# IOPower.net
KiCad netlist of a schematic drawn in Altium Designer
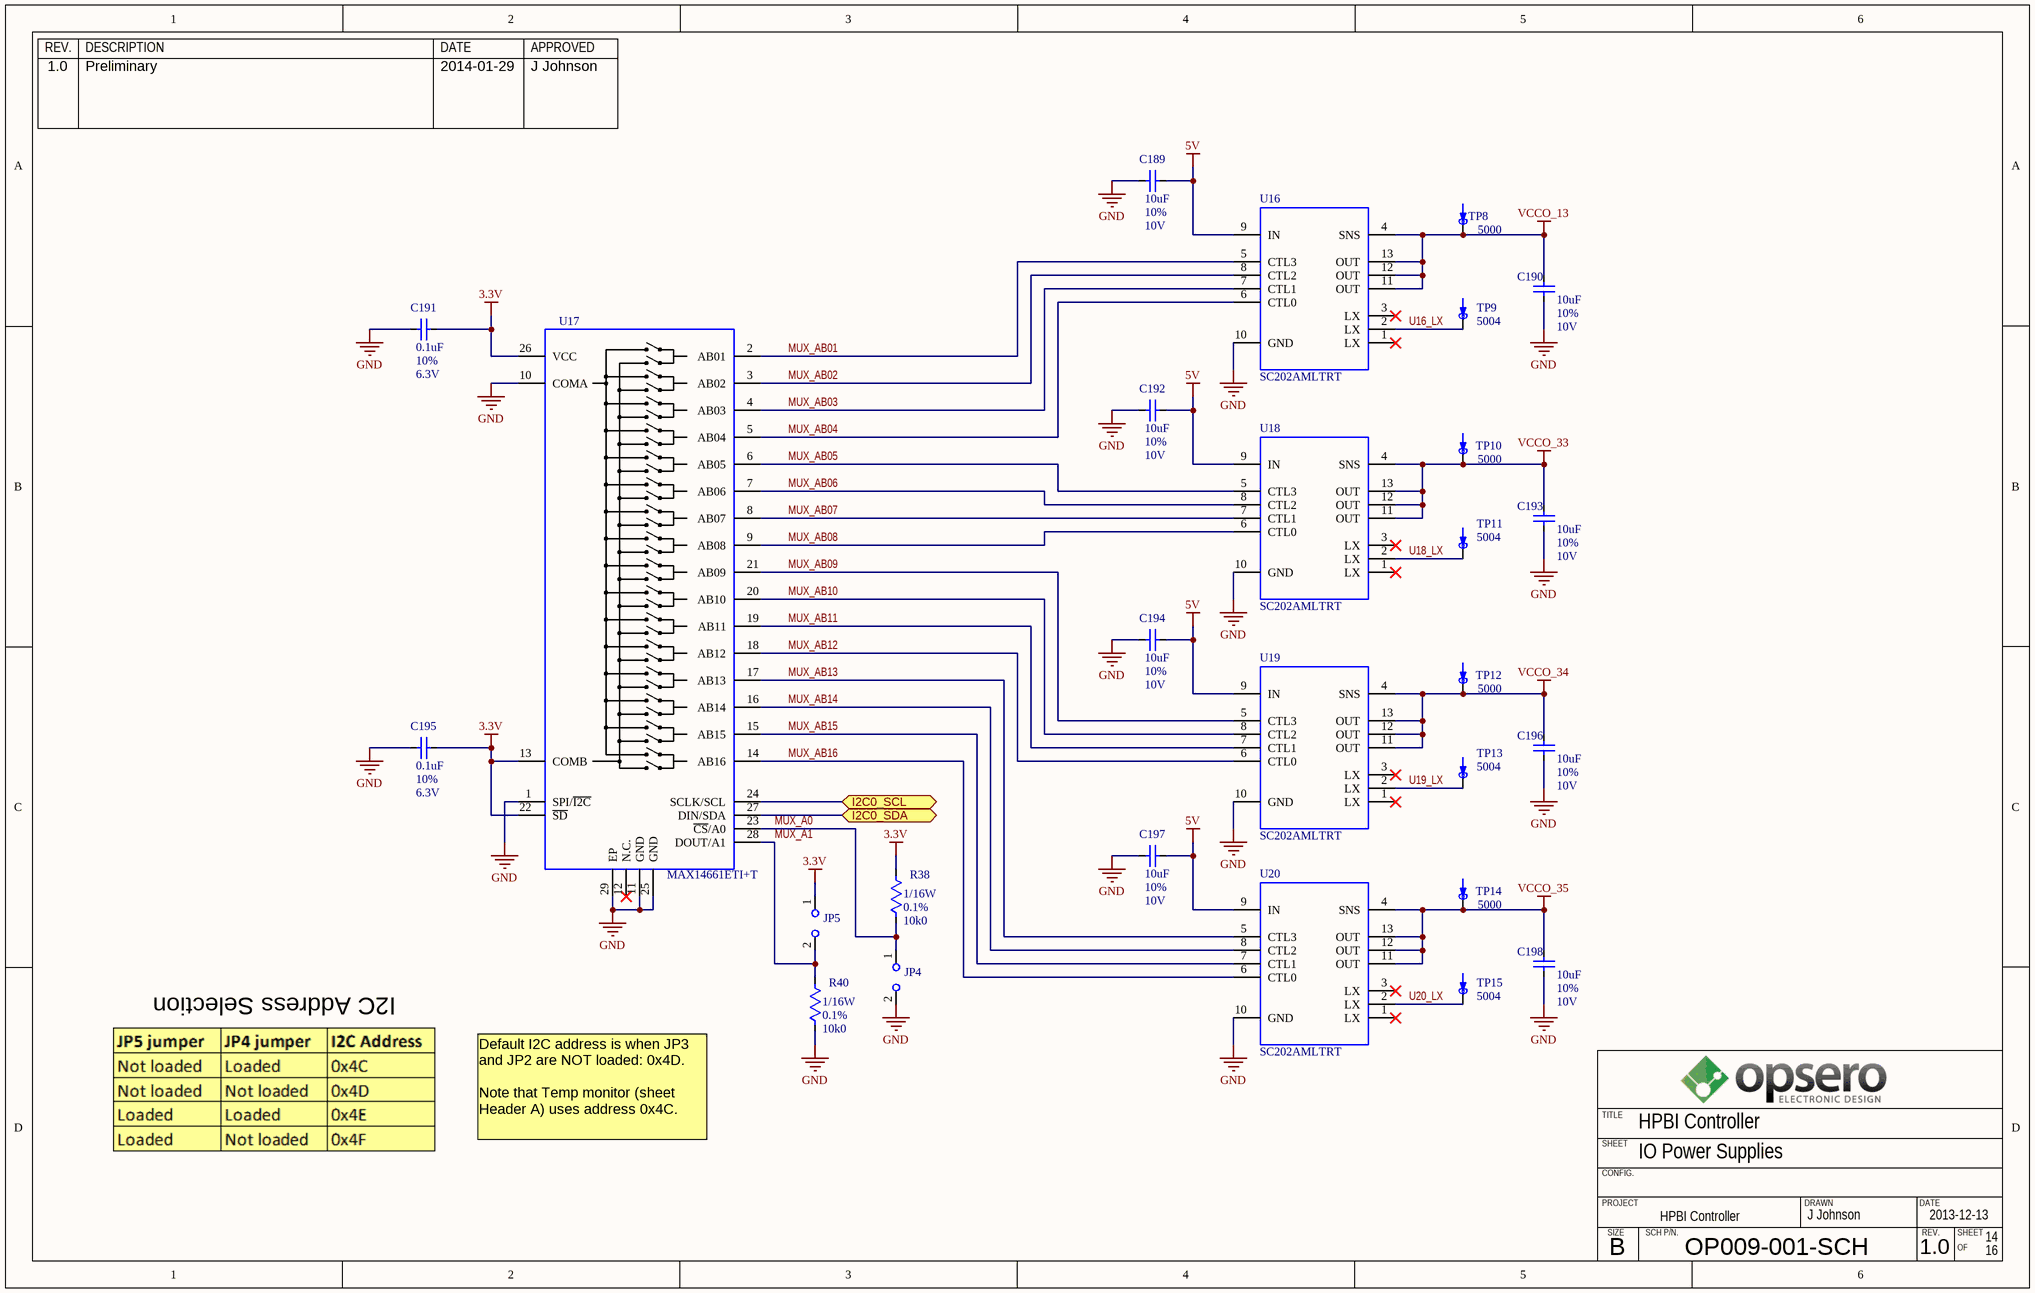
[diagram p0: IOPower.SchDoc]

(export (version "E")
  (design (tool "Eeschema 10.0.6"))
  (components
    (comp (ref "C189")
      (value "10uF")
      (footprint "CAPC1608X38N")
      (description "Capacitor ceramic, X5R, 10uF, 10V, 10%, -55 to +85 C, EIA0603")
      (fields
        (field (name "TOLERANCE") "10%")
        (field (name "VOLTAGE") "10V")
        (field (name "Comment") "CAPACITOR_NP_TYPE1")
      )
      (libsource (lib "parts") (part "CAPACITOR_NP_TYPE1"))
    )
    (comp (ref "C190")
      (value "10uF")
      (footprint "CAPC1608X38N")
      (description "Capacitor ceramic, X5R, 10uF, 10V, 10%, -55 to +85 C, EIA0603")
      (fields
        (field (name "TOLERANCE") "10%")
        (field (name "VOLTAGE") "10V")
        (field (name "Comment") "CAPACITOR_NP_TYPE1")
      )
      (libsource (lib "parts") (part "CAPACITOR_NP_TYPE1"))
    )
    (comp (ref "C191")
      (value "0.1uF")
      (footprint "CAPC0603X33N")
      (description "Capacitor ceramic, X5R, 0.1uF, 6.3V, 10%, -55 to +125 C, EIA0201")
      (fields
        (field (name "TOLERANCE") "10%")
        (field (name "VOLTAGE") "6.3V")
        (field (name "Comment") "CAPACITOR_NP_TYPE1")
      )
      (libsource (lib "parts") (part "CAPACITOR_NP_TYPE1"))
    )
    (comp (ref "C192")
      (value "10uF")
      (footprint "CAPC1608X38N")
      (description "Capacitor ceramic, X5R, 10uF, 10V, 10%, -55 to +85 C, EIA0603")
      (fields
        (field (name "TOLERANCE") "10%")
        (field (name "VOLTAGE") "10V")
        (field (name "Comment") "CAPACITOR_NP_TYPE1")
      )
      (libsource (lib "parts") (part "CAPACITOR_NP_TYPE1"))
    )
    (comp (ref "C193")
      (value "10uF")
      (footprint "CAPC1608X38N")
      (description "Capacitor ceramic, X5R, 10uF, 10V, 10%, -55 to +85 C, EIA0603")
      (fields
        (field (name "TOLERANCE") "10%")
        (field (name "VOLTAGE") "10V")
        (field (name "Comment") "CAPACITOR_NP_TYPE1")
      )
      (libsource (lib "parts") (part "CAPACITOR_NP_TYPE1"))
    )
    (comp (ref "C194")
      (value "10uF")
      (footprint "CAPC1608X38N")
      (description "Capacitor ceramic, X5R, 10uF, 10V, 10%, -55 to +85 C, EIA0603")
      (fields
        (field (name "TOLERANCE") "10%")
        (field (name "VOLTAGE") "10V")
        (field (name "Comment") "CAPACITOR_NP_TYPE1")
      )
      (libsource (lib "parts") (part "CAPACITOR_NP_TYPE1"))
    )
    (comp (ref "C195")
      (value "0.1uF")
      (footprint "CAPC0603X33N")
      (description "Capacitor ceramic, X5R, 0.1uF, 6.3V, 10%, -55 to +125 C, EIA0201")
      (fields
        (field (name "TOLERANCE") "10%")
        (field (name "VOLTAGE") "6.3V")
        (field (name "Comment") "CAPACITOR_NP_TYPE1")
      )
      (libsource (lib "parts") (part "CAPACITOR_NP_TYPE1"))
    )
    (comp (ref "C196")
      (value "10uF")
      (footprint "CAPC1608X38N")
      (description "Capacitor ceramic, X5R, 10uF, 10V, 10%, -55 to +85 C, EIA0603")
      (fields
        (field (name "TOLERANCE") "10%")
        (field (name "VOLTAGE") "10V")
        (field (name "Comment") "CAPACITOR_NP_TYPE1")
      )
      (libsource (lib "parts") (part "CAPACITOR_NP_TYPE1"))
    )
    (comp (ref "C197")
      (value "10uF")
      (footprint "CAPC1608X38N")
      (description "Capacitor ceramic, X5R, 10uF, 10V, 10%, -55 to +85 C, EIA0603")
      (fields
        (field (name "TOLERANCE") "10%")
        (field (name "VOLTAGE") "10V")
        (field (name "Comment") "CAPACITOR_NP_TYPE1")
      )
      (libsource (lib "parts") (part "CAPACITOR_NP_TYPE1"))
    )
    (comp (ref "C198")
      (value "10uF")
      (footprint "CAPC1608X38N")
      (description "Capacitor ceramic, X5R, 10uF, 10V, 10%, -55 to +85 C, EIA0603")
      (fields
        (field (name "TOLERANCE") "10%")
        (field (name "VOLTAGE") "10V")
        (field (name "Comment") "CAPACITOR_NP_TYPE1")
      )
      (libsource (lib "parts") (part "CAPACITOR_NP_TYPE1"))
    )
    (comp (ref "JP4")
      (value "JP_HDR2x1")
      (footprint "961102-6404-AR")
      (description "Jumper Header .100'', 2-pin, TH")
      (fields (field (name "POWER") "Pow") (field (name "VOLTAGE") "Vol"))
      (libsource (lib "parts") (part "JP_HDR2x1"))
    )
    (comp (ref "JP5")
      (value "JP_HDR2x1")
      (footprint "961102-6404-AR")
      (description "Jumper Header .100'', 2-pin, TH")
      (fields (field (name "POWER") "Pow") (field (name "VOLTAGE") "Vol"))
      (libsource (lib "parts") (part "JP_HDR2x1"))
    )
    (comp (ref "R38")
      (value "10k0")
      (footprint "RESC1005X33N")
      (description "Resistor, 10k0, 1/16W, 0.1%, -50 to +155 C, EIA0402")
      (fields (field (name "VOLTAGE") "50V") (field (name "POWER") "1/16W") (field (name "TOLERANCE") "0.1%"))
      (libsource (lib "parts") (part "RESISTOR_TYPE1"))
    )
    (comp (ref "R40")
      (value "10k0")
      (footprint "RESC1005X33N")
      (description "Resistor, 10k0, 1/16W, 0.1%, -50 to +155 C, EIA0402")
      (fields (field (name "VOLTAGE") "50V") (field (name "POWER") "1/16W") (field (name "TOLERANCE") "0.1%"))
      (libsource (lib "parts") (part "RESISTOR_TYPE1"))
    )
    (comp (ref "TP8")
      (value "5000")
      (footprint "KEY_5000")
      (description "Test point bead, red, Keystone Electronics, Thru-hole,")
      (fields (field (name "POWER") "Pow") (field (name "VOLTAGE") "Vol"))
      (libsource (lib "parts") (part "TEST_POINT_TYPE4"))
    )
    (comp (ref "TP9")
      (value "5004")
      (footprint "KEY_5004")
      (description "Test point bead, yellow, Keystone Electronics, Thru-hole,")
      (fields (field (name "POWER") "Pow") (field (name "VOLTAGE") "Vol"))
      (libsource (lib "parts") (part "TEST_POINT_TYPE4"))
    )
    (comp (ref "TP10")
      (value "5000")
      (footprint "KEY_5000")
      (description "Test point bead, red, Keystone Electronics, Thru-hole,")
      (fields (field (name "POWER") "Pow") (field (name "VOLTAGE") "Vol"))
      (libsource (lib "parts") (part "TEST_POINT_TYPE4"))
    )
    (comp (ref "TP11")
      (value "5004")
      (footprint "KEY_5004")
      (description "Test point bead, yellow, Keystone Electronics, Thru-hole,")
      (fields (field (name "POWER") "Pow") (field (name "VOLTAGE") "Vol"))
      (libsource (lib "parts") (part "TEST_POINT_TYPE4"))
    )
    (comp (ref "TP12")
      (value "5000")
      (footprint "KEY_5000")
      (description "Test point bead, red, Keystone Electronics, Thru-hole,")
      (fields (field (name "POWER") "Pow") (field (name "VOLTAGE") "Vol"))
      (libsource (lib "parts") (part "TEST_POINT_TYPE4"))
    )
    (comp (ref "TP13")
      (value "5004")
      (footprint "KEY_5004")
      (description "Test point bead, yellow, Keystone Electronics, Thru-hole,")
      (fields (field (name "POWER") "Pow") (field (name "VOLTAGE") "Vol"))
      (libsource (lib "parts") (part "TEST_POINT_TYPE4"))
    )
    (comp (ref "TP14")
      (value "5000")
      (footprint "KEY_5000")
      (description "Test point bead, red, Keystone Electronics, Thru-hole,")
      (fields (field (name "POWER") "Pow") (field (name "VOLTAGE") "Vol"))
      (libsource (lib "parts") (part "TEST_POINT_TYPE4"))
    )
    (comp (ref "TP15")
      (value "5004")
      (footprint "KEY_5004")
      (description "Test point bead, yellow, Keystone Electronics, Thru-hole,")
      (fields (field (name "POWER") "Pow") (field (name "VOLTAGE") "Vol"))
      (libsource (lib "parts") (part "TEST_POINT_TYPE4"))
    )
    (comp (ref "U16")
      (value "SC202AMLTRT")
      (footprint "QFN40P250X300X90-13N")
      (description "Regulator Step-down, 13-pin, 0.8V to 3.3V, 500mA, SMT, -40 to +85C, MLPQ-13")
      (fields (field (name "VOLTAGE") "0.8V to 3.3V") (field (name "MFG PART NUMBER 1") "SC202AMLTRT"))
      (libsource (lib "parts") (part "SC202AMLTRT"))
    )
    (comp (ref "U17")
      (value "MAX14661")
      (footprint "QFN40P400X400X75-29N")
      (description "Analog MUX, 16 to 2, BiCMOS")
      (fields (field (name "VOLTAGE") "+1.6V to +5.5V") (field (name "MFG PART NUMBER 1") "MAX14661ETI+T"))
      (libsource (lib "parts") (part "MAX14661"))
    )
    (comp (ref "U18")
      (value "SC202AMLTRT")
      (footprint "QFN40P250X300X90-13N")
      (description "Regulator Step-down, 13-pin, 0.8V to 3.3V, 500mA, SMT, -40 to +85C, MLPQ-13")
      (fields (field (name "VOLTAGE") "0.8V to 3.3V") (field (name "MFG PART NUMBER 1") "SC202AMLTRT"))
      (libsource (lib "parts") (part "SC202AMLTRT"))
    )
    (comp (ref "U19")
      (value "SC202AMLTRT")
      (footprint "QFN40P250X300X90-13N")
      (description "Regulator Step-down, 13-pin, 0.8V to 3.3V, 500mA, SMT, -40 to +85C, MLPQ-13")
      (fields (field (name "VOLTAGE") "0.8V to 3.3V") (field (name "MFG PART NUMBER 1") "SC202AMLTRT"))
      (libsource (lib "parts") (part "SC202AMLTRT"))
    )
    (comp (ref "U20")
      (value "SC202AMLTRT")
      (footprint "QFN40P250X300X90-13N")
      (description "Regulator Step-down, 13-pin, 0.8V to 3.3V, 500mA, SMT, -40 to +85C, MLPQ-13")
      (fields (field (name "VOLTAGE") "0.8V to 3.3V") (field (name "MFG PART NUMBER 1") "SC202AMLTRT"))
      (libsource (lib "parts") (part "SC202AMLTRT"))
    )
  )
  (nets
    (net (code "1") (name "/I2C0_SCL") (class "Default")
      (node (ref "U17") (pin "24") (pinfunction "SCLK/SCL_24") (pintype "passive"))
    )
    (net (code "2") (name "/I2C0_SDA") (class "Default")
      (node (ref "U17") (pin "27") (pinfunction "DIN/SDA_27") (pintype "passive"))
    )
    (net (code "3") (name "/MUX_A0") (class "Default")
      (node (ref "JP4") (pin "1") (pintype "passive"))
      (node (ref "R38") (pin "2") (pinfunction "2_2") (pintype "passive"))
      (node (ref "U17") (pin "23") (pinfunction "~{CS}/A0_23") (pintype "passive"))
    )
    (net (code "4") (name "/MUX_A1") (class "Default")
      (node (ref "JP5") (pin "2") (pintype "passive"))
      (node (ref "R40") (pin "1") (pinfunction "1_1") (pintype "passive"))
      (node (ref "U17") (pin "28") (pinfunction "DOUT/A1_28") (pintype "passive"))
    )
    (net (code "5") (name "/MUX_AB01") (class "Default")
      (node (ref "U16") (pin "5") (pinfunction "CTL3_5") (pintype "passive"))
      (node (ref "U17") (pin "2") (pinfunction "AB01_2") (pintype "passive"))
    )
    (net (code "6") (name "/MUX_AB02") (class "Default")
      (node (ref "U16") (pin "8") (pinfunction "CTL2_8") (pintype "passive"))
      (node (ref "U17") (pin "3") (pinfunction "AB02_3") (pintype "passive"))
    )
    (net (code "7") (name "/MUX_AB03") (class "Default")
      (node (ref "U16") (pin "7") (pinfunction "CTL1_7") (pintype "passive"))
      (node (ref "U17") (pin "4") (pinfunction "AB03_4") (pintype "passive"))
    )
    (net (code "8") (name "/MUX_AB04") (class "Default")
      (node (ref "U16") (pin "6") (pinfunction "CTL0_6") (pintype "passive"))
      (node (ref "U17") (pin "5") (pinfunction "AB04_5") (pintype "passive"))
    )
    (net (code "9") (name "/MUX_AB05") (class "Default")
      (node (ref "U17") (pin "6") (pinfunction "AB05_6") (pintype "passive"))
      (node (ref "U18") (pin "5") (pinfunction "CTL3_5") (pintype "passive"))
    )
    (net (code "10") (name "/MUX_AB06") (class "Default")
      (node (ref "U17") (pin "7") (pinfunction "AB06_7") (pintype "passive"))
      (node (ref "U18") (pin "8") (pinfunction "CTL2_8") (pintype "passive"))
    )
    (net (code "11") (name "/MUX_AB07") (class "Default")
      (node (ref "U17") (pin "8") (pinfunction "AB07_8") (pintype "passive"))
      (node (ref "U18") (pin "7") (pinfunction "CTL1_7") (pintype "passive"))
    )
    (net (code "12") (name "/MUX_AB08") (class "Default")
      (node (ref "U17") (pin "9") (pinfunction "AB08_9") (pintype "passive"))
      (node (ref "U18") (pin "6") (pinfunction "CTL0_6") (pintype "passive"))
    )
    (net (code "13") (name "/MUX_AB09") (class "Default")
      (node (ref "U17") (pin "21") (pinfunction "AB09_21") (pintype "passive"))
      (node (ref "U19") (pin "5") (pinfunction "CTL3_5") (pintype "passive"))
    )
    (net (code "14") (name "/MUX_AB10") (class "Default")
      (node (ref "U17") (pin "20") (pinfunction "AB10_20") (pintype "passive"))
      (node (ref "U19") (pin "8") (pinfunction "CTL2_8") (pintype "passive"))
    )
    (net (code "15") (name "/MUX_AB11") (class "Default")
      (node (ref "U17") (pin "19") (pinfunction "AB11_19") (pintype "passive"))
      (node (ref "U19") (pin "7") (pinfunction "CTL1_7") (pintype "passive"))
    )
    (net (code "16") (name "/MUX_AB12") (class "Default")
      (node (ref "U17") (pin "18") (pinfunction "AB12_18") (pintype "passive"))
      (node (ref "U19") (pin "6") (pinfunction "CTL0_6") (pintype "passive"))
    )
    (net (code "17") (name "/MUX_AB13") (class "Default")
      (node (ref "U17") (pin "17") (pinfunction "AB13_17") (pintype "passive"))
      (node (ref "U20") (pin "5") (pinfunction "CTL3_5") (pintype "passive"))
    )
    (net (code "18") (name "/MUX_AB14") (class "Default")
      (node (ref "U17") (pin "16") (pinfunction "AB14_16") (pintype "passive"))
      (node (ref "U20") (pin "8") (pinfunction "CTL2_8") (pintype "passive"))
    )
    (net (code "19") (name "/MUX_AB15") (class "Default")
      (node (ref "U17") (pin "15") (pinfunction "AB15_15") (pintype "passive"))
      (node (ref "U20") (pin "7") (pinfunction "CTL1_7") (pintype "passive"))
    )
    (net (code "20") (name "/MUX_AB16") (class "Default")
      (node (ref "U17") (pin "14") (pinfunction "AB16_14") (pintype "passive"))
      (node (ref "U20") (pin "6") (pinfunction "CTL0_6") (pintype "passive"))
    )
    (net (code "21") (name "/U16_LX") (class "Default")
      (node (ref "TP9") (pin "1") (pinfunction "1_1") (pintype "passive"))
      (node (ref "U16") (pin "2") (pinfunction "LX_2") (pintype "passive"))
    )
    (net (code "22") (name "/U18_LX") (class "Default")
      (node (ref "TP11") (pin "1") (pinfunction "1_1") (pintype "passive"))
      (node (ref "U18") (pin "2") (pinfunction "LX_2") (pintype "passive"))
    )
    (net (code "23") (name "/U19_LX") (class "Default")
      (node (ref "TP13") (pin "1") (pinfunction "1_1") (pintype "passive"))
      (node (ref "U19") (pin "2") (pinfunction "LX_2") (pintype "passive"))
    )
    (net (code "24") (name "/U20_LX") (class "Default")
      (node (ref "TP15") (pin "1") (pinfunction "1_1") (pintype "passive"))
      (node (ref "U20") (pin "2") (pinfunction "LX_2") (pintype "passive"))
    )
    (net (code "25") (name "3.3V") (class "Default")
      (node (ref "C191") (pin "1") (pinfunction "1_1") (pintype "passive"))
      (node (ref "C195") (pin "1") (pinfunction "1_1") (pintype "passive"))
      (node (ref "JP5") (pin "1") (pintype "passive"))
      (node (ref "R38") (pin "1") (pinfunction "1_1") (pintype "passive"))
      (node (ref "U17") (pin "13") (pinfunction "COMB_13") (pintype "passive"))
      (node (ref "U17") (pin "22") (pinfunction "~{SD}_22") (pintype "passive"))
      (node (ref "U17") (pin "26") (pinfunction "VCC_26") (pintype "passive"))
    )
    (net (code "26") (name "5V") (class "Default")
      (node (ref "C189") (pin "1") (pinfunction "1_1") (pintype "passive"))
      (node (ref "C192") (pin "1") (pinfunction "1_1") (pintype "passive"))
      (node (ref "C194") (pin "1") (pinfunction "1_1") (pintype "passive"))
      (node (ref "C197") (pin "1") (pinfunction "1_1") (pintype "passive"))
      (node (ref "U16") (pin "9") (pinfunction "IN_9") (pintype "passive"))
      (node (ref "U18") (pin "9") (pinfunction "IN_9") (pintype "passive"))
      (node (ref "U19") (pin "9") (pinfunction "IN_9") (pintype "passive"))
      (node (ref "U20") (pin "9") (pinfunction "IN_9") (pintype "passive"))
    )
    (net (code "27") (name "GND") (class "Default")
      (node (ref "C189") (pin "2") (pinfunction "2_2") (pintype "passive"))
      (node (ref "C190") (pin "2") (pinfunction "2_2") (pintype "passive"))
      (node (ref "C191") (pin "2") (pinfunction "2_2") (pintype "passive"))
      (node (ref "C192") (pin "2") (pinfunction "2_2") (pintype "passive"))
      (node (ref "C193") (pin "2") (pinfunction "2_2") (pintype "passive"))
      (node (ref "C194") (pin "2") (pinfunction "2_2") (pintype "passive"))
      (node (ref "C195") (pin "2") (pinfunction "2_2") (pintype "passive"))
      (node (ref "C196") (pin "2") (pinfunction "2_2") (pintype "passive"))
      (node (ref "C197") (pin "2") (pinfunction "2_2") (pintype "passive"))
      (node (ref "C198") (pin "2") (pinfunction "2_2") (pintype "passive"))
      (node (ref "JP4") (pin "2") (pintype "passive"))
      (node (ref "R40") (pin "2") (pinfunction "2_2") (pintype "passive"))
      (node (ref "U16") (pin "10") (pinfunction "GND_10") (pintype "passive"))
      (node (ref "U17") (pin "1") (pinfunction "SPI/~{I2C}_1") (pintype "passive"))
      (node (ref "U17") (pin "10") (pinfunction "COMA_10") (pintype "passive"))
      (node (ref "U17") (pin "11") (pinfunction "GND_11") (pintype "passive"))
      (node (ref "U17") (pin "25") (pinfunction "GND_25") (pintype "passive"))
      (node (ref "U17") (pin "29") (pinfunction "EP_29") (pintype "power_in"))
      (node (ref "U18") (pin "10") (pinfunction "GND_10") (pintype "passive"))
      (node (ref "U19") (pin "10") (pinfunction "GND_10") (pintype "passive"))
      (node (ref "U20") (pin "10") (pinfunction "GND_10") (pintype "passive"))
    )
    (net (code "28") (name "VCCO_13") (class "Default")
      (node (ref "C190") (pin "1") (pinfunction "1_1") (pintype "passive"))
      (node (ref "TP8") (pin "1") (pinfunction "1_1") (pintype "passive"))
      (node (ref "U16") (pin "11") (pinfunction "OUT_11") (pintype "passive"))
      (node (ref "U16") (pin "12") (pinfunction "OUT_12") (pintype "passive"))
      (node (ref "U16") (pin "13") (pinfunction "OUT_13") (pintype "passive"))
      (node (ref "U16") (pin "4") (pinfunction "SNS_4") (pintype "passive"))
    )
    (net (code "29") (name "VCCO_33") (class "Default")
      (node (ref "C193") (pin "1") (pinfunction "1_1") (pintype "passive"))
      (node (ref "TP10") (pin "1") (pinfunction "1_1") (pintype "passive"))
      (node (ref "U18") (pin "11") (pinfunction "OUT_11") (pintype "passive"))
      (node (ref "U18") (pin "12") (pinfunction "OUT_12") (pintype "passive"))
      (node (ref "U18") (pin "13") (pinfunction "OUT_13") (pintype "passive"))
      (node (ref "U18") (pin "4") (pinfunction "SNS_4") (pintype "passive"))
    )
    (net (code "30") (name "VCCO_34") (class "Default")
      (node (ref "C196") (pin "1") (pinfunction "1_1") (pintype "passive"))
      (node (ref "TP12") (pin "1") (pinfunction "1_1") (pintype "passive"))
      (node (ref "U19") (pin "11") (pinfunction "OUT_11") (pintype "passive"))
      (node (ref "U19") (pin "12") (pinfunction "OUT_12") (pintype "passive"))
      (node (ref "U19") (pin "13") (pinfunction "OUT_13") (pintype "passive"))
      (node (ref "U19") (pin "4") (pinfunction "SNS_4") (pintype "passive"))
    )
    (net (code "31") (name "VCCO_35") (class "Default")
      (node (ref "C198") (pin "1") (pinfunction "1_1") (pintype "passive"))
      (node (ref "TP14") (pin "1") (pinfunction "1_1") (pintype "passive"))
      (node (ref "U20") (pin "11") (pinfunction "OUT_11") (pintype "passive"))
      (node (ref "U20") (pin "12") (pinfunction "OUT_12") (pintype "passive"))
      (node (ref "U20") (pin "13") (pinfunction "OUT_13") (pintype "passive"))
      (node (ref "U20") (pin "4") (pinfunction "SNS_4") (pintype "passive"))
    )
    (net (code "32") (name "unconnected-(U16-LX-Pad1)") (class "Default")
      (node (ref "U16") (pin "1") (pinfunction "LX_1") (pintype "passive+no_connect"))
    )
    (net (code "33") (name "unconnected-(U16-LX-Pad3)") (class "Default")
      (node (ref "U16") (pin "3") (pinfunction "LX_3") (pintype "passive+no_connect"))
    )
    (net (code "34") (name "unconnected-(U17-N.C.-Pad12)") (class "Default")
      (node (ref "U17") (pin "12") (pinfunction "N.C._12") (pintype "passive+no_connect"))
    )
    (net (code "35") (name "unconnected-(U18-LX-Pad1)") (class "Default")
      (node (ref "U18") (pin "1") (pinfunction "LX_1") (pintype "passive+no_connect"))
    )
    (net (code "36") (name "unconnected-(U18-LX-Pad3)") (class "Default")
      (node (ref "U18") (pin "3") (pinfunction "LX_3") (pintype "passive+no_connect"))
    )
    (net (code "37") (name "unconnected-(U19-LX-Pad1)") (class "Default")
      (node (ref "U19") (pin "1") (pinfunction "LX_1") (pintype "passive+no_connect"))
    )
    (net (code "38") (name "unconnected-(U19-LX-Pad3)") (class "Default")
      (node (ref "U19") (pin "3") (pinfunction "LX_3") (pintype "passive+no_connect"))
    )
    (net (code "39") (name "unconnected-(U20-LX-Pad1)") (class "Default")
      (node (ref "U20") (pin "1") (pinfunction "LX_1") (pintype "passive+no_connect"))
    )
    (net (code "40") (name "unconnected-(U20-LX-Pad3)") (class "Default")
      (node (ref "U20") (pin "3") (pinfunction "LX_3") (pintype "passive+no_connect"))
    )
  )
)
